# 4_2_-__2024-11-22.net
KiCad netlist of a schematic drawn in Altium Designer
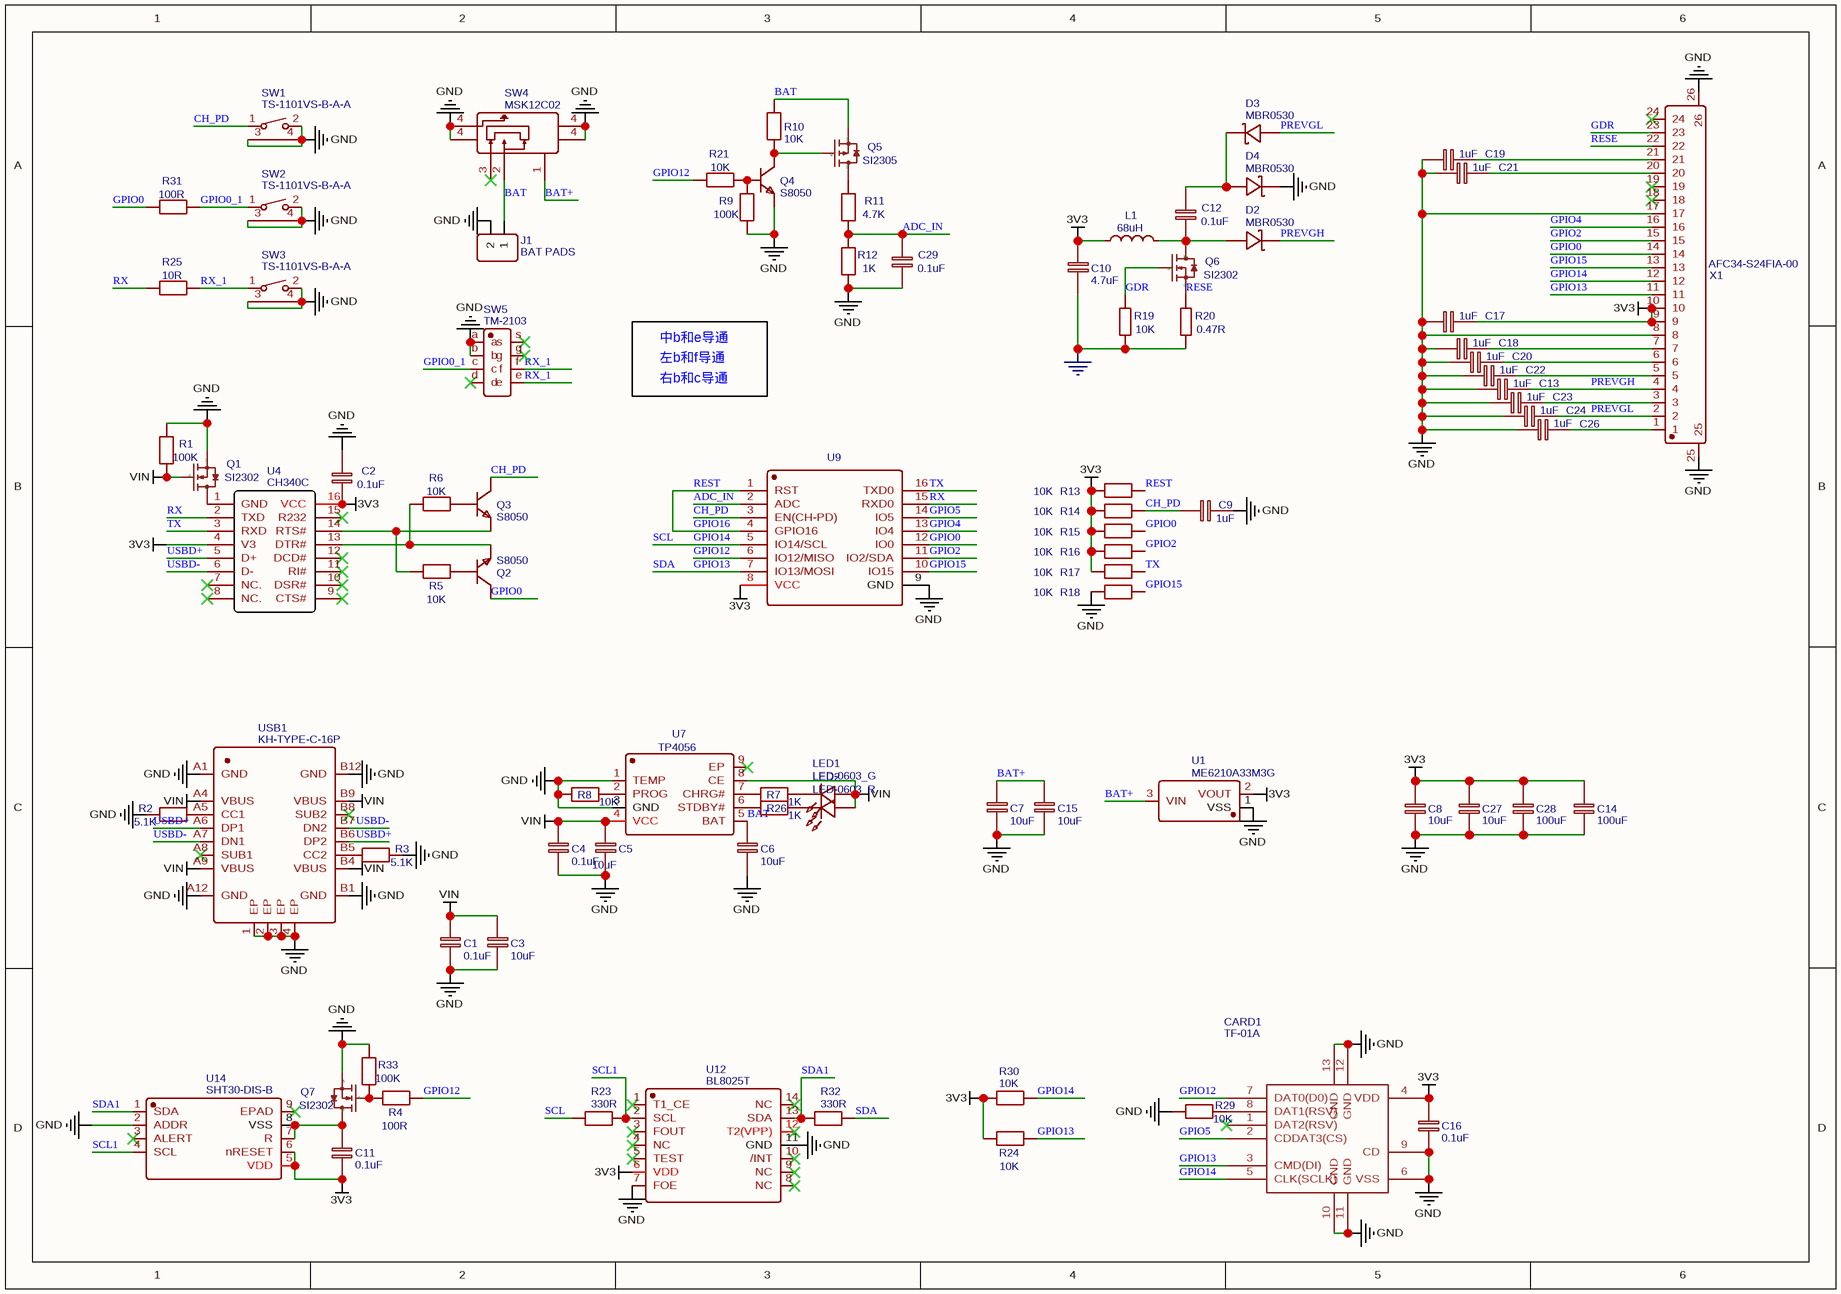
[diagram p0: 4.2寸墨水屏-兼容甘草酸不酸_2024-11-22.schdoc]

(export (version "E")
  (design (tool "Eeschema 10.0.6"))
  (components
    (comp (ref "C1")
      (value "0.1uF")
      (fields (field (name "CONTRIBUTOR") "LCEDA_Lib"))
      (libsource (lib "altium-import") (part "root_3_0.1uF_"))
    )
    (comp (ref "C2")
      (value "0.1uF")
      (fields (field (name "CONTRIBUTOR") "LCEDA_Lib"))
      (libsource (lib "altium-import") (part "root_1_0.1uF_"))
    )
    (comp (ref "C3")
      (value "10uF")
      (fields (field (name "CONTRIBUTOR") "LCEDA_Lib"))
      (libsource (lib "altium-import") (part "root_3_10uF_"))
    )
    (comp (ref "C4")
      (value "0.1uF")
      (fields (field (name "CONTRIBUTOR") "LCEDA_Lib"))
      (libsource (lib "altium-import") (part "root_3_0.1uF_"))
    )
    (comp (ref "C5")
      (value "10uF")
      (fields (field (name "CONTRIBUTOR") "LCEDA_Lib"))
      (libsource (lib "altium-import") (part "root_3_10uF_"))
    )
    (comp (ref "C6")
      (value "10uF")
      (fields (field (name "CONTRIBUTOR") "LCEDA_Lib"))
      (libsource (lib "altium-import") (part "root_3_10uF_"))
    )
    (comp (ref "C7")
      (value "10uF")
      (fields (field (name "CONTRIBUTOR") "LCEDA_Lib"))
      (libsource (lib "altium-import") (part "root_3_10uF_"))
    )
    (comp (ref "C8")
      (value "10uF")
      (fields (field (name "CONTRIBUTOR") "LCEDA_Lib"))
      (libsource (lib "altium-import") (part "root_1_10uF_"))
    )
    (comp (ref "C9")
      (value "1uF")
      (fields (field (name "CONTRIBUTOR") "LCEDA_Lib"))
      (libsource (lib "altium-import") (part "root_0_1uF_"))
    )
    (comp (ref "C10")
      (value "4.7uF")
      (fields
        (field (name "MANUFACTURER PART") "CL10A475MP5LNNC")
        (field (name "MANUFACTURER") "Samsung Electro-Mechanics")
      )
      (libsource (lib "altium-import") (part "root_0_4.7uF_"))
    )
    (comp (ref "C11")
      (value "0.1uF")
      (fields (field (name "CONTRIBUTOR") "LCEDA_Lib"))
      (libsource (lib "altium-import") (part "root_1_0.1uF_"))
    )
    (comp (ref "C12")
      (value "0.1uF")
      (fields (field (name "CONTRIBUTOR") "LCEDA_Lib"))
      (libsource (lib "altium-import") (part "root_1_0.1uF_"))
    )
    (comp (ref "C13")
      (value "1uF")
      (fields (field (name "CONTRIBUTOR") "LCEDA_Lib"))
      (libsource (lib "altium-import") (part "root_0_1uF_"))
    )
    (comp (ref "C14")
      (value "100uF")
      (fields (field (name "CONTRIBUTOR") "LCEDA_Lib"))
      (libsource (lib "altium-import") (part "root_1_100uF_"))
    )
    (comp (ref "C15")
      (value "10uF")
      (fields (field (name "CONTRIBUTOR") "LCEDA_Lib"))
      (libsource (lib "altium-import") (part "root_3_10uF_"))
    )
    (comp (ref "C16")
      (value "0.1uF")
      (fields (field (name "CONTRIBUTOR") "LCEDA_Lib"))
      (libsource (lib "altium-import") (part "root_1_0.1uF_"))
    )
    (comp (ref "C17")
      (value "1uF")
      (fields (field (name "CONTRIBUTOR") "LCEDA_Lib"))
      (libsource (lib "altium-import") (part "root_0_1uF_"))
    )
    (comp (ref "C18")
      (value "1uF")
      (fields (field (name "CONTRIBUTOR") "LCEDA_Lib"))
      (libsource (lib "altium-import") (part "root_0_1uF_"))
    )
    (comp (ref "C19")
      (value "1uF")
      (fields (field (name "CONTRIBUTOR") "LCEDA_Lib"))
      (libsource (lib "altium-import") (part "root_0_1uF_"))
    )
    (comp (ref "C20")
      (value "1uF")
      (fields (field (name "CONTRIBUTOR") "LCEDA_Lib"))
      (libsource (lib "altium-import") (part "root_0_1uF_"))
    )
    (comp (ref "C21")
      (value "1uF")
      (fields (field (name "CONTRIBUTOR") "LCEDA_Lib"))
      (libsource (lib "altium-import") (part "root_0_1uF_"))
    )
    (comp (ref "C22")
      (value "1uF")
      (fields (field (name "CONTRIBUTOR") "LCEDA_Lib"))
      (libsource (lib "altium-import") (part "root_0_1uF_"))
    )
    (comp (ref "C23")
      (value "1uF")
      (fields (field (name "CONTRIBUTOR") "LCEDA_Lib"))
      (libsource (lib "altium-import") (part "root_0_1uF_"))
    )
    (comp (ref "C24")
      (value "1uF")
      (fields (field (name "CONTRIBUTOR") "LCEDA_Lib"))
      (libsource (lib "altium-import") (part "root_0_1uF_"))
    )
    (comp (ref "C26")
      (value "1uF")
      (fields (field (name "CONTRIBUTOR") "LCEDA_Lib"))
      (libsource (lib "altium-import") (part "root_0_1uF_"))
    )
    (comp (ref "C27")
      (value "10uF")
      (fields (field (name "CONTRIBUTOR") "LCEDA_Lib"))
      (libsource (lib "altium-import") (part "root_1_10uF_"))
    )
    (comp (ref "C28")
      (value "100uF")
      (fields (field (name "CONTRIBUTOR") "LCEDA_Lib"))
      (libsource (lib "altium-import") (part "root_1_100uF_"))
    )
    (comp (ref "C29")
      (value "0.1uF")
      (fields (field (name "CONTRIBUTOR") "LCEDA_Lib"))
      (libsource (lib "altium-import") (part "root_1_0.1uF_"))
    )
    (comp (ref "CARD1")
      (value "TF-01A")
      (fields (field (name "MANUFACTURER") "韩国韩荣"))
      (libsource (lib "altium-import") (part "root_0_TF-01A_"))
    )
    (comp (ref "D2") (value "MBR0530") (libsource (lib "altium-import") (part "root_0_MBR0530_")))
    (comp (ref "D3") (value "MBR0530") (libsource (lib "altium-import") (part "root_2_MBR0530_")))
    (comp (ref "D4") (value "MBR0530") (libsource (lib "altium-import") (part "root_0_MBR0530_")))
    (comp (ref "J1")
      (value "BAT PADS")
      (fields (field (name "CONTRIBUTOR") "LCEDA_Lib"))
      (libsource (lib "altium-import") (part "root_3_BAT PADS_"))
    )
    (comp (ref "L1")
      (value "68uH")
      (fields
        (field (name "MANUFACTURER") "DMBJ(振宝佳)")
        (field (name "MANUFACTURER PART") "CD32-680M")
        (field (name "CONTRIBUTOR") "LCSC")
      )
      (libsource (lib "altium-import") (part "root_0_68uH_"))
    )
    (comp (ref "LED1")
      (value "LED-0603_G")
      (fields
        (field (name "MANUFACTURER") "EVERLIGHT(台湾亿光)")
        (field (name "MANUFACTURER PART") "19-217/GHC-YR1S2/3T")
        (field (name "CONTRIBUTOR") "LCEDA_Lib")
      )
      (libsource (lib "altium-import") (part "root_2_LED-0603_G_"))
    )
    (comp (ref "LED2")
      (value "LED-0603_R")
      (fields
        (field (name "MANUFACTURER") "EVERLIGHT(台湾亿光)")
        (field (name "MANUFACTURER PART") "19-217/R6C-AL1M2VY/3T")
        (field (name "CONTRIBUTOR") "LCEDA_01")
      )
      (libsource (lib "altium-import") (part "root_2_LED-0603_R_"))
    )
    (comp (ref "Q1")
      (value "SI2302")
      (fields (field (name "MANUFACTURER") "Hottech") (field (name "CONTRIBUTOR") "LCSC"))
      (libsource (lib "") (part "root_2_SI2302__1"))
    )
    (comp (ref "Q2")
      (value "S8050")
      (fields (field (name "MANUFACTURER") "CJ(江苏长电/长晶)") (field (name "MANUFACTURER PART") "S8050 J3Y"))
      (libsource (lib "") (part "root_0_S8050__1"))
    )
    (comp (ref "Q3")
      (value "S8050")
      (fields (field (name "MANUFACTURER") "CJ(江苏长电/长晶)") (field (name "MANUFACTURER PART") "S8050 J3Y"))
      (libsource (lib "altium-import") (part "root_0_S8050_"))
    )
    (comp (ref "Q4")
      (value "S8050")
      (fields (field (name "MANUFACTURER") "CJ(江苏长电/长晶)") (field (name "MANUFACTURER PART") "S8050 J3Y"))
      (libsource (lib "altium-import") (part "root_0_S8050_"))
    )
    (comp (ref "Q5")
      (value "SI2305")
      (fields (field (name "MANUFACTURER") "Hottech(合科泰)") (field (name "CONTRIBUTOR") "LCSC"))
      (libsource (lib "altium-import") (part "root_0_SI2305_"))
    )
    (comp (ref "Q6")
      (value "SI2302")
      (fields (field (name "MANUFACTURER") "Hottech") (field (name "CONTRIBUTOR") "LCSC"))
      (libsource (lib "altium-import") (part "root_2_SI2302_"))
    )
    (comp (ref "Q7")
      (value "SI2302")
      (fields (field (name "MANUFACTURER") "Hottech") (field (name "CONTRIBUTOR") "LCSC"))
      (libsource (lib "altium-import") (part "root_0_SI2302_"))
    )
    (comp (ref "R1")
      (value "100K")
      (fields (field (name "CONTRIBUTOR") "LCEDA_Lib"))
      (libsource (lib "altium-import") (part "root_1_100K_"))
    )
    (comp (ref "R2")
      (value "5.1K")
      (fields (field (name "CONTRIBUTOR") "LCEDA_Lib"))
      (libsource (lib "altium-import") (part "root_0_5.1K_"))
    )
    (comp (ref "R3")
      (value "5.1K")
      (fields (field (name "CONTRIBUTOR") "LCEDA_Lib"))
      (libsource (lib "altium-import") (part "root_0_5.1K_"))
    )
    (comp (ref "R4")
      (value "100R")
      (fields (field (name "CONTRIBUTOR") "LCEDA_Lib"))
      (libsource (lib "altium-import") (part "root_2_100R_"))
    )
    (comp (ref "R5")
      (value "10K")
      (fields (field (name "CONTRIBUTOR") "LCEDA_Lib"))
      (libsource (lib "altium-import") (part "root_0_10K_"))
    )
    (comp (ref "R6")
      (value "10K")
      (fields (field (name "CONTRIBUTOR") "LCEDA_Lib"))
      (libsource (lib "altium-import") (part "root_0_10K_"))
    )
    (comp (ref "R7")
      (value "1K")
      (fields (field (name "CONTRIBUTOR") "LCEDA_Lib"))
      (libsource (lib "altium-import") (part "root_0_1K_"))
    )
    (comp (ref "R8")
      (value "10K")
      (fields (field (name "CONTRIBUTOR") "LCEDA_Lib"))
      (libsource (lib "altium-import") (part "root_0_10K_"))
    )
    (comp (ref "R9")
      (value "100K")
      (fields (field (name "CONTRIBUTOR") "LCEDA_Lib"))
      (libsource (lib "altium-import") (part "root_1_100K_"))
    )
    (comp (ref "R10")
      (value "10K")
      (fields (field (name "CONTRIBUTOR") "LCEDA_Lib"))
      (libsource (lib "") (part "root_1_10K__1"))
    )
    (comp (ref "R11")
      (value "4.7K")
      (fields (field (name "CONTRIBUTOR") "LCEDA_Lib"))
      (libsource (lib "altium-import") (part "root_1_4.7K_"))
    )
    (comp (ref "R12")
      (value "1K")
      (fields (field (name "CONTRIBUTOR") "LCEDA_Lib"))
      (libsource (lib "altium-import") (part "root_1_1K_"))
    )
    (comp (ref "R13")
      (value "10K")
      (fields (field (name "CONTRIBUTOR") "LCEDA_Lib"))
      (libsource (lib "altium-import") (part "root_0_10K_"))
    )
    (comp (ref "R14")
      (value "10K")
      (fields (field (name "CONTRIBUTOR") "LCEDA_Lib"))
      (libsource (lib "altium-import") (part "root_0_10K_"))
    )
    (comp (ref "R15")
      (value "10K")
      (fields (field (name "CONTRIBUTOR") "LCEDA_Lib"))
      (libsource (lib "altium-import") (part "root_0_10K_"))
    )
    (comp (ref "R16")
      (value "10K")
      (fields (field (name "CONTRIBUTOR") "LCEDA_Lib"))
      (libsource (lib "altium-import") (part "root_0_10K_"))
    )
    (comp (ref "R17")
      (value "10K")
      (fields (field (name "CONTRIBUTOR") "LCEDA_Lib"))
      (libsource (lib "altium-import") (part "root_0_10K_"))
    )
    (comp (ref "R18")
      (value "10K")
      (fields (field (name "CONTRIBUTOR") "LCEDA_Lib"))
      (libsource (lib "altium-import") (part "root_0_10K_"))
    )
    (comp (ref "R19")
      (value "10K")
      (fields
        (field (name "MANUFACTURER PART") "CRCW060310K0JNEA")
        (field (name "MANUFACTURER") "Vishay Intertech")
      )
      (libsource (lib "altium-import") (part "root_1_10K_"))
    )
    (comp (ref "R20")
      (value "0.47R")
      (fields
        (field (name "MANUFACTURER PART") "CR0603F0R47P05")
        (field (name "MANUFACTURER") "Ever Ohms Tech")
      )
      (libsource (lib "altium-import") (part "root_1_0.47R_"))
    )
    (comp (ref "R21")
      (value "10K")
      (fields (field (name "CONTRIBUTOR") "LCEDA_Lib"))
      (libsource (lib "altium-import") (part "root_0_10K_"))
    )
    (comp (ref "R23")
      (value "330R")
      (fields (field (name "CONTRIBUTOR") "LCEDA_Lib"))
      (libsource (lib "altium-import") (part "root_0_330R_"))
    )
    (comp (ref "R24")
      (value "10K")
      (fields (field (name "CONTRIBUTOR") "LCEDA_Lib"))
      (libsource (lib "altium-import") (part "root_2_10K_"))
    )
    (comp (ref "R25")
      (value "10R")
      (fields (field (name "CONTRIBUTOR") "LCEDA_Lib"))
      (libsource (lib "altium-import") (part "root_0_10R_"))
    )
    (comp (ref "R26")
      (value "1K")
      (fields (field (name "CONTRIBUTOR") "LCEDA_Lib"))
      (libsource (lib "altium-import") (part "root_0_1K_"))
    )
    (comp (ref "R29")
      (value "10K")
      (fields (field (name "CONTRIBUTOR") "LCEDA_Lib"))
      (libsource (lib "altium-import") (part "root_0_10K_"))
    )
    (comp (ref "R30")
      (value "10K")
      (fields (field (name "CONTRIBUTOR") "LCEDA_Lib"))
      (libsource (lib "altium-import") (part "root_2_10K_"))
    )
    (comp (ref "R31")
      (value "100R")
      (fields (field (name "CONTRIBUTOR") "LCEDA_Lib"))
      (libsource (lib "altium-import") (part "root_0_100R_"))
    )
    (comp (ref "R32")
      (value "330R")
      (fields (field (name "CONTRIBUTOR") "LCEDA_Lib"))
      (libsource (lib "altium-import") (part "root_0_330R_"))
    )
    (comp (ref "R33")
      (value "100K")
      (fields (field (name "CONTRIBUTOR") "LCEDA_Lib"))
      (libsource (lib "altium-import") (part "root_1_100K_"))
    )
    (comp (ref "SW1")
      (value "TS-1101VS-B-A-A")
      (fields (field (name "MANUFACTURER") "XKB Enterprise") (field (name "CONTRIBUTOR") "LCSC"))
      (libsource (lib "altium-import") (part "root_0_TS-1101VS-B-A-A_"))
    )
    (comp (ref "SW2")
      (value "TS-1101VS-B-A-A")
      (fields (field (name "MANUFACTURER") "XKB Enterprise") (field (name "CONTRIBUTOR") "LCSC"))
      (libsource (lib "altium-import") (part "root_0_TS-1101VS-B-A-A_"))
    )
    (comp (ref "SW3")
      (value "TS-1101VS-B-A-A")
      (fields (field (name "MANUFACTURER") "XKB Enterprise") (field (name "CONTRIBUTOR") "LCSC"))
      (libsource (lib "altium-import") (part "root_0_TS-1101VS-B-A-A_"))
    )
    (comp (ref "SW4")
      (value "MSK12C02")
      (fields (field (name "MANUFACTURER") "SHOU HAN") (field (name "CONTRIBUTOR") "LCSC"))
      (libsource (lib "altium-import") (part "root_2_MSK12C02_"))
    )
    (comp (ref "SW5")
      (value "TM-2103")
      (fields (field (name "MANUFACTURER") "XKB Connectivity(中国星坤)") (field (name "CONTRIBUTOR") "LCSC"))
      (libsource (lib "altium-import") (part "root_0_TM-2103_"))
    )
    (comp (ref "U1")
      (value "ME6210A33M3G")
      (fields (field (name "MANUFACTURER") "MICRONE(南京微盟)") (field (name "CONTRIBUTOR") "LCSC"))
      (libsource (lib "altium-import") (part "root_2_ME6210A33M3G_"))
    )
    (comp (ref "U4")
      (value "CH340C")
      (fields (field (name "MANUFACTURER") "WCH(南京沁恒)"))
      (libsource (lib "altium-import") (part "root_0_CH340C_"))
    )
    (comp (ref "U7")
      (value "TP4056")
      (fields (field (name "MANUFACTURER") "UMW(友台半导体)") (field (name "CONTRIBUTOR") "LCSC"))
      (libsource (lib "altium-import") (part "root_0_TP4056_"))
    )
    (comp (ref "U9")
      (value "ESP8266模组标注版")
      (fields (field (name "CONTRIBUTOR") "SakuraNeko"))
      (libsource (lib "altium-import") (part "root_0_ESP8266模组标注版_"))
    )
    (comp (ref "U12")
      (value "BL8025T")
      (fields (field (name "MANUFACTURER") "BL"))
      (libsource (lib "altium-import") (part "root_0_BL8025T_"))
    )
    (comp (ref "U14")
      (value "SHT30-DIS-B")
      (fields
        (field (name "MANUFACTURER") "Sensirion(瑞士盛思锐)")
        (field (name "MANUFACTURER PART") "SHT30-DIS-B2.5KS")
      )
      (libsource (lib "altium-import") (part "root_0_SHT30-DIS-B_"))
    )
    (comp (ref "USB1")
      (value "KH-TYPE-C-16P")
      (fields (field (name "MANUFACTURER") "kinghelm(金航标)") (field (name "CONTRIBUTOR") "LCSC"))
      (libsource (lib "altium-import") (part "root_0_KH-TYPE-C-16P_"))
    )
    (comp (ref "X1")
      (value "AFC34-S24FIA-00")
      (fields (field (name "MANUFACTURER") "JS(钜硕电子)") (field (name "CONTRIBUTOR") "LCSC"))
      (libsource (lib "altium-import") (part "root_0_AFC34-S24FIA-00_"))
    )
  )
  (nets
    (net (code "1") (name "/ADC_IN") (class "Default")
      (node (ref "C29") (pin "2") (pinfunction "2_2") (pintype "passive"))
      (node (ref "R11") (pin "1") (pinfunction "1_1") (pintype "passive"))
      (node (ref "R12") (pin "2") (pinfunction "2_2") (pintype "passive"))
      (node (ref "U9") (pin "2") (pinfunction "ADC_2") (pintype "passive"))
    )
    (net (code "2") (name "/BAT") (class "Default")
      (node (ref "C6") (pin "1") (pinfunction "1_1") (pintype "passive"))
      (node (ref "J1") (pin "1") (pinfunction "1_1") (pintype "passive"))
      (node (ref "Q5") (pin "2") (pinfunction "S_2") (pintype "passive"))
      (node (ref "R10") (pin "2") (pinfunction "2_2") (pintype "passive"))
      (node (ref "SW4") (pin "2") (pinfunction "2_2") (pintype "passive"))
      (node (ref "U7") (pin "5") (pinfunction "BAT_5") (pintype "passive"))
    )
    (net (code "3") (name "/BAT+") (class "Default")
      (node (ref "C15") (pin "1") (pinfunction "1_1") (pintype "passive"))
      (node (ref "C7") (pin "1") (pinfunction "1_1") (pintype "passive"))
      (node (ref "SW4") (pin "1") (pinfunction "1_1") (pintype "passive"))
      (node (ref "U1") (pin "3") (pinfunction "VIN_3") (pintype "passive"))
    )
    (net (code "4") (name "/CH_PD") (class "Default")
      (node (ref "C9") (pin "1") (pinfunction "1_1") (pintype "passive"))
      (node (ref "Q3") (pin "3") (pinfunction "C_3") (pintype "passive"))
      (node (ref "R14") (pin "2") (pinfunction "2_2") (pintype "passive"))
      (node (ref "SW1") (pin "1") (pinfunction "1_1") (pintype "passive"))
      (node (ref "U9") (pin "3") (pinfunction "EN(CH-PD)_3") (pintype "passive"))
    )
    (net (code "5") (name "/GDR") (class "Default")
      (node (ref "Q6") (pin "1") (pinfunction "G_1") (pintype "passive"))
      (node (ref "R19") (pin "2") (pinfunction "2_2") (pintype "passive"))
      (node (ref "X1") (pin "23") (pinfunction "23_23") (pintype "passive"))
    )
    (net (code "6") (name "/GPIO0") (class "Default")
      (node (ref "Q2") (pin "3") (pinfunction "C_3") (pintype "passive"))
      (node (ref "R15") (pin "2") (pinfunction "2_2") (pintype "passive"))
      (node (ref "R31") (pin "1") (pinfunction "1_1") (pintype "passive"))
      (node (ref "U9") (pin "12") (pinfunction "IO0_12") (pintype "passive"))
      (node (ref "X1") (pin "14") (pinfunction "14_14") (pintype "passive"))
    )
    (net (code "7") (name "/GPIO0_1") (class "Default")
      (node (ref "R31") (pin "2") (pinfunction "2_2") (pintype "passive"))
      (node (ref "SW2") (pin "1") (pinfunction "1_1") (pintype "passive"))
      (node (ref "SW5") (pin "c") (pinfunction "c_c") (pintype "passive"))
    )
    (net (code "8") (name "/GPIO2") (class "Default")
      (node (ref "R16") (pin "2") (pinfunction "2_2") (pintype "passive"))
      (node (ref "U9") (pin "11") (pinfunction "IO2/SDA_11") (pintype "passive"))
      (node (ref "X1") (pin "15") (pinfunction "15_15") (pintype "passive"))
    )
    (net (code "9") (name "/GPIO4") (class "Default")
      (node (ref "U9") (pin "13") (pinfunction "IO4_13") (pintype "passive"))
      (node (ref "X1") (pin "16") (pinfunction "16_16") (pintype "passive"))
    )
    (net (code "10") (name "/GPIO5") (class "Default")
      (node (ref "CARD1") (pin "2") (pinfunction "CDDAT3(CS)_2") (pintype "passive"))
      (node (ref "U9") (pin "14") (pinfunction "IO5_14") (pintype "passive"))
    )
    (net (code "11") (name "/GPIO12") (class "Default")
      (node (ref "CARD1") (pin "7") (pinfunction "DAT0(D0)_7") (pintype "passive"))
      (node (ref "R21") (pin "1") (pinfunction "1_1") (pintype "passive"))
      (node (ref "R4") (pin "1") (pinfunction "1_1") (pintype "passive"))
      (node (ref "U9") (pin "6") (pinfunction "IO12/MISO_6") (pintype "passive"))
    )
    (net (code "12") (name "/GPIO13") (class "Default")
      (node (ref "CARD1") (pin "3") (pinfunction "CMD(DI)_3") (pintype "passive"))
      (node (ref "R24") (pin "1") (pinfunction "1_1") (pintype "passive"))
      (node (ref "R32") (pin "2") (pinfunction "2_2") (pintype "passive"))
      (node (ref "U9") (pin "7") (pinfunction "IO13/MOSI_7") (pintype "passive"))
      (node (ref "X1") (pin "11") (pinfunction "11_11") (pintype "passive"))
    )
    (net (code "13") (name "/GPIO14") (class "Default")
      (node (ref "CARD1") (pin "5") (pinfunction "CLK(SCLK)_5") (pintype "passive"))
      (node (ref "R23") (pin "1") (pinfunction "1_1") (pintype "passive"))
      (node (ref "R30") (pin "1") (pinfunction "1_1") (pintype "passive"))
      (node (ref "U9") (pin "5") (pinfunction "IO14/SCL_5") (pintype "passive"))
      (node (ref "X1") (pin "12") (pinfunction "12_12") (pintype "passive"))
    )
    (net (code "14") (name "/GPIO15") (class "Default")
      (node (ref "R18") (pin "2") (pinfunction "2_2") (pintype "passive"))
      (node (ref "U9") (pin "10") (pinfunction "IO15_10") (pintype "passive"))
      (node (ref "X1") (pin "13") (pinfunction "13_13") (pintype "passive"))
    )
    (net (code "15") (name "/GPIO16") (class "Default")
      (node (ref "R13") (pin "2") (pinfunction "2_2") (pintype "passive"))
      (node (ref "U9") (pin "1") (pinfunction "RST_1") (pintype "passive"))
      (node (ref "U9") (pin "4") (pinfunction "GPIO16_4") (pintype "passive"))
    )
    (net (code "16") (name "/PREVGH") (class "Default")
      (node (ref "C13") (pin "2") (pinfunction "2_2") (pintype "passive"))
      (node (ref "D2") (pin "2") (pinfunction "K_2") (pintype "passive"))
      (node (ref "X1") (pin "4") (pinfunction "4_4") (pintype "passive"))
    )
    (net (code "17") (name "/PREVGL") (class "Default")
      (node (ref "C24") (pin "2") (pinfunction "2_2") (pintype "passive"))
      (node (ref "D3") (pin "1") (pinfunction "A_1") (pintype "passive"))
      (node (ref "X1") (pin "2") (pinfunction "2_2") (pintype "passive"))
    )
    (net (code "18") (name "/RESE") (class "Default")
      (node (ref "Q6") (pin "2") (pinfunction "S_2") (pintype "passive"))
      (node (ref "R20") (pin "2") (pinfunction "2_2") (pintype "passive"))
      (node (ref "X1") (pin "22") (pinfunction "22_22") (pintype "passive"))
    )
    (net (code "19") (name "/RX") (class "Default")
      (node (ref "R25") (pin "1") (pinfunction "1_1") (pintype "passive"))
      (node (ref "U4") (pin "2") (pinfunction "TXD_2") (pintype "passive"))
      (node (ref "U9") (pin "15") (pinfunction "RXD0_15") (pintype "passive"))
    )
    (net (code "20") (name "/RX_1") (class "Default")
      (node (ref "R25") (pin "2") (pinfunction "2_2") (pintype "passive"))
      (node (ref "SW3") (pin "1") (pinfunction "1_1") (pintype "passive"))
      (node (ref "SW5") (pin "e") (pinfunction "e_e") (pintype "passive"))
      (node (ref "SW5") (pin "f") (pinfunction "f_f") (pintype "passive"))
    )
    (net (code "21") (name "/SCL1") (class "Default")
      (node (ref "R23") (pin "2") (pinfunction "2_2") (pintype "passive"))
      (node (ref "U12") (pin "2") (pinfunction "SCL_2") (pintype "passive"))
      (node (ref "U14") (pin "4") (pinfunction "SCL_4") (pintype "passive"))
    )
    (net (code "22") (name "/SDA1") (class "Default")
      (node (ref "R32") (pin "1") (pinfunction "1_1") (pintype "passive"))
      (node (ref "U12") (pin "13") (pinfunction "SDA_13") (pintype "passive"))
      (node (ref "U14") (pin "1") (pinfunction "SDA_1") (pintype "passive"))
    )
    (net (code "23") (name "/TX") (class "Default")
      (node (ref "R17") (pin "2") (pinfunction "2_2") (pintype "passive"))
      (node (ref "U4") (pin "3") (pinfunction "RXD_3") (pintype "passive"))
      (node (ref "U9") (pin "16") (pinfunction "TXD0_16") (pintype "passive"))
    )
    (net (code "24") (name "/USBD+") (class "Default")
      (node (ref "U4") (pin "5") (pinfunction "D+_5") (pintype "passive"))
      (node (ref "USB1") (pin "A6") (pinfunction "DP1_A6") (pintype "passive"))
      (node (ref "USB1") (pin "B6") (pinfunction "DP2_B6") (pintype "passive"))
    )
    (net (code "25") (name "/USBD-") (class "Default")
      (node (ref "U4") (pin "6") (pinfunction "D-_6") (pintype "passive"))
      (node (ref "USB1") (pin "A7") (pinfunction "DN1_A7") (pintype "passive"))
      (node (ref "USB1") (pin "B7") (pinfunction "DN2_B7") (pintype "passive"))
    )
    (net (code "26") (name "3V3") (class "Default")
      (node (ref "C10") (pin "1") (pinfunction "1_1") (pintype "passive"))
      (node (ref "C11") (pin "1") (pinfunction "1_1") (pintype "passive"))
      (node (ref "C14") (pin "2") (pinfunction "2_2") (pintype "passive"))
      (node (ref "C16") (pin "2") (pinfunction "2_2") (pintype "passive"))
      (node (ref "C17") (pin "2") (pinfunction "2_2") (pintype "passive"))
      (node (ref "C2") (pin "1") (pinfunction "1_1") (pintype "passive"))
      (node (ref "C27") (pin "2") (pinfunction "2_2") (pintype "passive"))
      (node (ref "C28") (pin "2") (pinfunction "2_2") (pintype "passive"))
      (node (ref "C8") (pin "2") (pinfunction "2_2") (pintype "passive"))
      (node (ref "CARD1") (pin "4") (pinfunction "VDD_4") (pintype "passive"))
      (node (ref "L1") (pin "1") (pinfunction "1_1") (pintype "passive"))
      (node (ref "R13") (pin "1") (pinfunction "1_1") (pintype "passive"))
      (node (ref "R14") (pin "1") (pinfunction "1_1") (pintype "passive"))
      (node (ref "R15") (pin "1") (pinfunction "1_1") (pintype "passive"))
      (node (ref "R16") (pin "1") (pinfunction "1_1") (pintype "passive"))
      (node (ref "R17") (pin "1") (pinfunction "1_1") (pintype "passive"))
      (node (ref "R24") (pin "2") (pinfunction "2_2") (pintype "passive"))
      (node (ref "R30") (pin "2") (pinfunction "2_2") (pintype "passive"))
      (node (ref "U1") (pin "2") (pinfunction "VOUT_2") (pintype "passive"))
      (node (ref "U12") (pin "6") (pinfunction "VDD_6") (pintype "passive"))
      (node (ref "U14") (pin "5") (pinfunction "VDD_5") (pintype "passive"))
      (node (ref "U14") (pin "6") (pinfunction "nRESET_6") (pintype "passive"))
      (node (ref "U4") (pin "16") (pinfunction "VCC_16") (pintype "passive"))
      (node (ref "U4") (pin "4") (pinfunction "V3_4") (pintype "passive"))
      (node (ref "U9") (pin "8") (pinfunction "VCC_8") (pintype "passive"))
      (node (ref "X1") (pin "10") (pinfunction "10_10") (pintype "passive"))
      (node (ref "X1") (pin "9") (pinfunction "9_9") (pintype "passive"))
    )
    (net (code "27") (name "GND") (class "Default")
      (node (ref "C1") (pin "2") (pinfunction "2_2") (pintype "passive"))
      (node (ref "C10") (pin "2") (pinfunction "2_2") (pintype "passive"))
      (node (ref "C13") (pin "1") (pinfunction "1_1") (pintype "passive"))
      (node (ref "C14") (pin "1") (pinfunction "1_1") (pintype "passive"))
      (node (ref "C15") (pin "2") (pinfunction "2_2") (pintype "passive"))
      (node (ref "C16") (pin "1") (pinfunction "1_1") (pintype "passive"))
      (node (ref "C17") (pin "1") (pinfunction "1_1") (pintype "passive"))
      (node (ref "C18") (pin "1") (pinfunction "1_1") (pintype "passive"))
      (node (ref "C19") (pin "1") (pinfunction "1_1") (pintype "passive"))
      (node (ref "C2") (pin "2") (pinfunction "2_2") (pintype "passive"))
      (node (ref "C20") (pin "1") (pinfunction "1_1") (pintype "passive"))
      (node (ref "C21") (pin "1") (pinfunction "1_1") (pintype "passive"))
      (node (ref "C22") (pin "1") (pinfunction "1_1") (pintype "passive"))
      (node (ref "C23") (pin "1") (pinfunction "1_1") (pintype "passive"))
      (node (ref "C24") (pin "1") (pinfunction "1_1") (pintype "passive"))
      (node (ref "C26") (pin "1") (pinfunction "1_1") (pintype "passive"))
      (node (ref "C27") (pin "1") (pinfunction "1_1") (pintype "passive"))
      (node (ref "C28") (pin "1") (pinfunction "1_1") (pintype "passive"))
      (node (ref "C29") (pin "1") (pinfunction "1_1") (pintype "passive"))
      (node (ref "C3") (pin "2") (pinfunction "2_2") (pintype "passive"))
      (node (ref "C4") (pin "2") (pinfunction "2_2") (pintype "passive"))
      (node (ref "C5") (pin "2") (pinfunction "2_2") (pintype "passive"))
      (node (ref "C6") (pin "2") (pinfunction "2_2") (pintype "passive"))
      (node (ref "C7") (pin "2") (pinfunction "2_2") (pintype "passive"))
      (node (ref "C8") (pin "1") (pinfunction "1_1") (pintype "passive"))
      (node (ref "C9") (pin "2") (pinfunction "2_2") (pintype "passive"))
      (node (ref "CARD1") (pin "10") (pinfunction "GND_10") (pintype "passive"))
      (node (ref "CARD1") (pin "11") (pinfunction "GND_11") (pintype "passive"))
      (node (ref "CARD1") (pin "12") (pinfunction "GND_12") (pintype "passive"))
      (node (ref "CARD1") (pin "13") (pinfunction "GND_13") (pintype "passive"))
      (node (ref "CARD1") (pin "6") (pinfunction "VSS_6") (pintype "passive"))
      (node (ref "CARD1") (pin "9") (pinfunction "CD_9") (pintype "passive"))
      (node (ref "D4") (pin "2") (pinfunction "K_2") (pintype "passive"))
      (node (ref "J1") (pin "2") (pinfunction "2_2") (pintype "passive"))
      (node (ref "Q1") (pin "2") (pinfunction "S_2") (pintype "passive"))
      (node (ref "Q4") (pin "2") (pinfunction "E_2") (pintype "passive"))
      (node (ref "Q7") (pin "2") (pinfunction "S_2") (pintype "passive"))
      (node (ref "R1") (pin "2") (pinfunction "2_2") (pintype "passive"))
      (node (ref "R12") (pin "1") (pinfunction "1_1") (pintype "passive"))
      (node (ref "R18") (pin "1") (pinfunction "1_1") (pintype "passive"))
      (node (ref "R19") (pin "1") (pinfunction "1_1") (pintype "passive"))
      (node (ref "R2") (pin "1") (pinfunction "1_1") (pintype "passive"))
      (node (ref "R20") (pin "1") (pinfunction "1_1") (pintype "passive"))
      (node (ref "R29") (pin "1") (pinfunction "1_1") (pintype "passive"))
      (node (ref "R3") (pin "2") (pinfunction "2_2") (pintype "passive"))
      (node (ref "R33") (pin "2") (pinfunction "2_2") (pintype "passive"))
      (node (ref "R8") (pin "1") (pinfunction "1_1") (pintype "passive"))
      (node (ref "R9") (pin "1") (pinfunction "1_1") (pintype "passive"))
      (node (ref "SW1") (pin "2") (pinfunction "2_2") (pintype "passive"))
      (node (ref "SW1") (pin "3") (pinfunction "3_3") (pintype "passive"))
      (node (ref "SW1") (pin "4") (pinfunction "4_4") (pintype "passive"))
      (node (ref "SW2") (pin "2") (pinfunction "2_2") (pintype "passive"))
      (node (ref "SW2") (pin "3") (pinfunction "3_3") (pintype "passive"))
      (node (ref "SW2") (pin "4") (pinfunction "4_4") (pintype "passive"))
      (node (ref "SW3") (pin "2") (pinfunction "2_2") (pintype "passive"))
      (node (ref "SW3") (pin "3") (pinfunction "3_3") (pintype "passive"))
      (node (ref "SW3") (pin "4") (pinfunction "4_4") (pintype "passive"))
      (node (ref "SW4") (pin "4") (pinfunction "4_4") (pintype "passive"))
      (node (ref "SW5") (pin "a") (pinfunction "a_a") (pintype "passive"))
      (node (ref "SW5") (pin "b") (pinfunction "b_b") (pintype "passive"))
      (node (ref "U1") (pin "1") (pinfunction "VSS_1") (pintype "passive"))
      (node (ref "U12") (pin "11") (pinfunction "GND_11") (pintype "passive"))
      (node (ref "U12") (pin "7") (pinfunction "FOE_7") (pintype "passive"))
      (node (ref "U14") (pin "2") (pinfunction "ADDR_2") (pintype "passive"))
      (node (ref "U7") (pin "1") (pinfunction "TEMP_1") (pintype "passive"))
      (node (ref "U7") (pin "3") (pinfunction "GND_3") (pintype "passive"))
      (node (ref "U9") (pin "9") (pinfunction "GND_9") (pintype "passive"))
      (node (ref "USB1") (pin "1") (pinfunction "EP_1") (pintype "passive"))
      (node (ref "USB1") (pin "2") (pinfunction "EP_2") (pintype "passive"))
      (node (ref "USB1") (pin "3") (pinfunction "EP_3") (pintype "passive"))
      (node (ref "USB1") (pin "4") (pinfunction "EP_4") (pintype "passive"))
      (node (ref "USB1") (pin "A1") (pinfunction "GND_A1") (pintype "passive"))
      (node (ref "USB1") (pin "A12") (pinfunction "GND_A12") (pintype "passive"))
      (node (ref "USB1") (pin "B1") (pinfunction "GND_B1") (pintype "passive"))
      (node (ref "USB1") (pin "B12") (pinfunction "GND_B12") (pintype "passive"))
      (node (ref "X1") (pin "17") (pinfunction "17_17") (pintype "passive"))
      (node (ref "X1") (pin "25") (pinfunction "25_25") (pintype "passive"))
      (node (ref "X1") (pin "26") (pinfunction "26_26") (pintype "passive"))
      (node (ref "X1") (pin "8") (pinfunction "8_8") (pintype "passive"))
    )
    (net (code "28") (name "Net-(C18-Pad2)") (class "Default")
      (node (ref "C18") (pin "2") (pinfunction "2_2") (pintype "passive"))
      (node (ref "X1") (pin "7") (pinfunction "7_7") (pintype "passive"))
    )
    (net (code "29") (name "Net-(C19-Pad2)") (class "Default")
      (node (ref "C19") (pin "2") (pinfunction "2_2") (pintype "passive"))
      (node (ref "X1") (pin "21") (pinfunction "21_21") (pintype "passive"))
    )
    (net (code "30") (name "Net-(C20-Pad2)") (class "Default")
      (node (ref "C20") (pin "2") (pinfunction "2_2") (pintype "passive"))
      (node (ref "X1") (pin "6") (pinfunction "6_6") (pintype "passive"))
    )
    (net (code "31") (name "Net-(C21-Pad2)") (class "Default")
      (node (ref "C21") (pin "2") (pinfunction "2_2") (pintype "passive"))
      (node (ref "X1") (pin "20") (pinfunction "20_20") (pintype "passive"))
    )
    (net (code "32") (name "Net-(C22-Pad2)") (class "Default")
      (node (ref "C22") (pin "2") (pinfunction "2_2") (pintype "passive"))
      (node (ref "X1") (pin "5") (pinfunction "5_5") (pintype "passive"))
    )
    (net (code "33") (name "Net-(C23-Pad2)") (class "Default")
      (node (ref "C23") (pin "2") (pinfunction "2_2") (pintype "passive"))
      (node (ref "X1") (pin "3") (pinfunction "3_3") (pintype "passive"))
    )
    (net (code "34") (name "Net-(C26-Pad2)") (class "Default")
      (node (ref "C26") (pin "2") (pinfunction "2_2") (pintype "passive"))
      (node (ref "X1") (pin "1") (pinfunction "1_1") (pintype "passive"))
    )
    (net (code "35") (name "Net-(CARD1-DAT1(RSV))") (class "Default")
      (node (ref "CARD1") (pin "8") (pinfunction "DAT1(RSV)_8") (pintype "passive"))
      (node (ref "R29") (pin "2") (pinfunction "2_2") (pintype "passive"))
    )
    (net (code "36") (name "Net-(D2-A)") (class "Default")
      (node (ref "C12") (pin "1") (pinfunction "1_1") (pintype "passive"))
      (node (ref "D2") (pin "1") (pinfunction "A_1") (pintype "passive"))
      (node (ref "L1") (pin "2") (pinfunction "2_2") (pintype "passive"))
      (node (ref "Q6") (pin "3") (pinfunction "D_3") (pintype "passive"))
    )
    (net (code "37") (name "Net-(D3-K)") (class "Default")
      (node (ref "C12") (pin "2") (pinfunction "2_2") (pintype "passive"))
      (node (ref "D3") (pin "2") (pinfunction "K_2") (pintype "passive"))
      (node (ref "D4") (pin "1") (pinfunction "A_1") (pintype "passive"))
    )
    (net (code "38") (name "Net-(LED1-Pad2)") (class "Default")
      (node (ref "LED1") (pin "2") (pinfunction "2_2") (pintype "passive"))
      (node (ref "R7") (pin "2") (pinfunction "2_2") (pintype "passive"))
    )
    (net (code "39") (name "Net-(LED2-Pad2)") (class "Default")
      (node (ref "LED2") (pin "2") (pinfunction "2_2") (pintype "passive"))
      (node (ref "R26") (pin "2") (pinfunction "2_2") (pintype "passive"))
    )
    (net (code "40") (name "Net-(Q1-D)") (class "Default")
      (node (ref "Q1") (pin "3") (pinfunction "D_3") (pintype "passive"))
      (node (ref "U4") (pin "1") (pinfunction "GND_1") (pintype "passive"))
    )
    (net (code "41") (name "Net-(Q2-B)") (class "Default")
      (node (ref "Q2") (pin "1") (pinfunction "B_1") (pintype "passive"))
      (node (ref "R5") (pin "2") (pinfunction "2_2") (pintype "passive"))
    )
    (net (code "42") (name "Net-(Q2-E)") (class "Default")
      (node (ref "Q2") (pin "2") (pinfunction "E_2") (pintype "passive"))
      (node (ref "R6") (pin "1") (pinfunction "1_1") (pintype "passive"))
      (node (ref "U4") (pin "13") (pinfunction "DTR#_13") (pintype "passive"))
    )
    (net (code "43") (name "Net-(Q3-B)") (class "Default")
      (node (ref "Q3") (pin "1") (pinfunction "B_1") (pintype "passive"))
      (node (ref "R6") (pin "2") (pinfunction "2_2") (pintype "passive"))
    )
    (net (code "44") (name "Net-(Q3-E)") (class "Default")
      (node (ref "Q3") (pin "2") (pinfunction "E_2") (pintype "passive"))
      (node (ref "R5") (pin "1") (pinfunction "1_1") (pintype "passive"))
      (node (ref "U4") (pin "14") (pinfunction "RTS#_14") (pintype "passive"))
    )
    (net (code "45") (name "Net-(Q4-B)") (class "Default")
      (node (ref "Q4") (pin "1") (pinfunction "B_1") (pintype "passive"))
      (node (ref "R21") (pin "2") (pinfunction "2_2") (pintype "passive"))
      (node (ref "R9") (pin "2") (pinfunction "2_2") (pintype "passive"))
    )
    (net (code "46") (name "Net-(Q4-C)") (class "Default")
      (node (ref "Q4") (pin "3") (pinfunction "C_3") (pintype "passive"))
      (node (ref "Q5") (pin "1") (pinfunction "G_1") (pintype "passive"))
      (node (ref "R10") (pin "1") (pinfunction "1_1") (pintype "passive"))
    )
    (net (code "47") (name "Net-(Q5-D)") (class "Default")
      (node (ref "Q5") (pin "3") (pinfunction "D_3") (pintype "passive"))
      (node (ref "R11") (pin "2") (pinfunction "2_2") (pintype "passive"))
    )
    (net (code "48") (name "Net-(Q7-D)") (class "Default")
      (node (ref "C11") (pin "2") (pinfunction "2_2") (pintype "passive"))
      (node (ref "Q7") (pin "3") (pinfunction "D_3") (pintype "passive"))
      (node (ref "U14") (pin "7") (pinfunction "R_7") (pintype "passive"))
      (node (ref "U14") (pin "8") (pinfunction "VSS_8") (pintype "passive"))
    )
    (net (code "49") (name "Net-(Q7-G)") (class "Default")
      (node (ref "Q7") (pin "1") (pinfunction "G_1") (pintype "passive"))
      (node (ref "R33") (pin "1") (pinfunction "1_1") (pintype "passive"))
      (node (ref "R4") (pin "2") (pinfunction "2_2") (pintype "passive"))
    )
    (net (code "50") (name "Net-(U7-CHRG#)") (class "Default")
      (node (ref "R7") (pin "1") (pinfunction "1_1") (pintype "passive"))
      (node (ref "U7") (pin "7") (pinfunction "CHRG#_7") (pintype "passive"))
    )
    (net (code "51") (name "Net-(U7-PROG)") (class "Default")
      (node (ref "R8") (pin "2") (pinfunction "2_2") (pintype "passive"))
      (node (ref "U7") (pin "2") (pinfunction "PROG_2") (pintype "passive"))
    )
    (net (code "52") (name "Net-(U7-STDBY#)") (class "Default")
      (node (ref "R26") (pin "1") (pinfunction "1_1") (pintype "passive"))
      (node (ref "U7") (pin "6") (pinfunction "STDBY#_6") (pintype "passive"))
    )
    (net (code "53") (name "Net-(USB1-CC1)") (class "Default")
      (node (ref "R2") (pin "2") (pinfunction "2_2") (pintype "passive"))
      (node (ref "USB1") (pin "A5") (pinfunction "CC1_A5") (pintype "passive"))
    )
    (net (code "54") (name "Net-(USB1-CC2)") (class "Default")
      (node (ref "R3") (pin "1") (pinfunction "1_1") (pintype "passive"))
      (node (ref "USB1") (pin "B5") (pinfunction "CC2_B5") (pintype "passive"))
    )
    (net (code "55") (name "VIN") (class "Default")
      (node (ref "C1") (pin "1") (pinfunction "1_1") (pintype "passive"))
      (node (ref "C3") (pin "1") (pinfunction "1_1") (pintype "passive"))
      (node (ref "C4") (pin "1") (pinfunction "1_1") (pintype "passive"))
      (node (ref "C5") (pin "1") (pinfunction "1_1") (pintype "passive"))
      (node (ref "LED1") (pin "1") (pinfunction "1_1") (pintype "passive"))
      (node (ref "LED2") (pin "1") (pinfunction "1_1") (pintype "passive"))
      (node (ref "Q1") (pin "1") (pinfunction "G_1") (pintype "passive"))
      (node (ref "R1") (pin "1") (pinfunction "1_1") (pintype "passive"))
      (node (ref "U7") (pin "4") (pinfunction "VCC_4") (pintype "passive"))
      (node (ref "U7") (pin "8") (pinfunction "CE_8") (pintype "passive"))
      (node (ref "USB1") (pin "A4") (pinfunction "VBUS_A4") (pintype "passive"))
      (node (ref "USB1") (pin "A9") (pinfunction "VBUS_A9") (pintype "passive"))
      (node (ref "USB1") (pin "B4") (pinfunction "VBUS_B4") (pintype "passive"))
      (node (ref "USB1") (pin "B9") (pinfunction "VBUS_B9") (pintype "passive"))
    )
    (net (code "56") (name "unconnected-(CARD1-DAT2(RSV)-Pad1)") (class "Default")
      (node (ref "CARD1") (pin "1") (pinfunction "DAT2(RSV)_1") (pintype "passive+no_connect"))
    )
    (net (code "57") (name "unconnected-(SW4-Pad3)") (class "Default")
      (node (ref "SW4") (pin "3") (pinfunction "3_3") (pintype "passive+no_connect"))
    )
    (net (code "58") (name "unconnected-(SW5-Padd)") (class "Default")
      (node (ref "SW5") (pin "d") (pinfunction "d_d") (pintype "passive+no_connect"))
    )
    (net (code "59") (name "unconnected-(SW5-Padg)") (class "Default")
      (node (ref "SW5") (pin "g") (pinfunction "g_g") (pintype "passive+no_connect"))
    )
    (net (code "60") (name "unconnected-(SW5-Pads)") (class "Default")
      (node (ref "SW5") (pin "s") (pinfunction "s_s") (pintype "passive+no_connect"))
    )
    (net (code "61") (name "unconnected-(U4-CTS#-Pad9)") (class "Default")
      (node (ref "U4") (pin "9") (pinfunction "CTS#_9") (pintype "passive+no_connect"))
    )
    (net (code "62") (name "unconnected-(U4-DCD#-Pad12)") (class "Default")
      (node (ref "U4") (pin "12") (pinfunction "DCD#_12") (pintype "passive+no_connect"))
    )
    (net (code "63") (name "unconnected-(U4-DSR#-Pad10)") (class "Default")
      (node (ref "U4") (pin "10") (pinfunction "DSR#_10") (pintype "passive+no_connect"))
    )
    (net (code "64") (name "unconnected-(U4-NC.-Pad7)") (class "Default")
      (node (ref "U4") (pin "7") (pinfunction "NC._7") (pintype "passive+no_connect"))
    )
    (net (code "65") (name "unconnected-(U4-NC.-Pad8)") (class "Default")
      (node (ref "U4") (pin "8") (pinfunction "NC._8") (pintype "passive+no_connect"))
    )
    (net (code "66") (name "unconnected-(U4-R232-Pad15)") (class "Default")
      (node (ref "U4") (pin "15") (pinfunction "R232_15") (pintype "passive+no_connect"))
    )
    (net (code "67") (name "unconnected-(U4-RI#-Pad11)") (class "Default")
      (node (ref "U4") (pin "11") (pinfunction "RI#_11") (pintype "passive+no_connect"))
    )
    (net (code "68") (name "unconnected-(U7-EP-Pad9)") (class "Default")
      (node (ref "U7") (pin "9") (pinfunction "EP_9") (pintype "passive+no_connect"))
    )
    (net (code "69") (name "unconnected-(U12-FOUT-Pad3)") (class "Default")
      (node (ref "U12") (pin "3") (pinfunction "FOUT_3") (pintype "passive+no_connect"))
    )
    (net (code "70") (name "unconnected-(U12-NC-Pad4)") (class "Default")
      (node (ref "U12") (pin "4") (pinfunction "NC_4") (pintype "passive+no_connect"))
    )
    (net (code "71") (name "unconnected-(U12-NC-Pad8)") (class "Default")
      (node (ref "U12") (pin "8") (pinfunction "NC_8") (pintype "passive+no_connect"))
    )
    (net (code "72") (name "unconnected-(U12-NC-Pad9)") (class "Default")
      (node (ref "U12") (pin "9") (pinfunction "NC_9") (pintype "passive+no_connect"))
    )
    (net (code "73") (name "unconnected-(U12-NC-Pad14)") (class "Default")
      (node (ref "U12") (pin "14") (pinfunction "NC_14") (pintype "passive+no_connect"))
    )
    (net (code "74") (name "unconnected-(U12-T1_CE-Pad1)") (class "Default")
      (node (ref "U12") (pin "1") (pinfunction "T1_CE_1") (pintype "passive+no_connect"))
    )
    (net (code "75") (name "unconnected-(U12-T2(VPP)-Pad12)") (class "Default")
      (node (ref "U12") (pin "12") (pinfunction "T2(VPP)_12") (pintype "passive+no_connect"))
    )
    (net (code "76") (name "unconnected-(U12-TEST-Pad5)") (class "Default")
      (node (ref "U12") (pin "5") (pinfunction "TEST_5") (pintype "passive+no_connect"))
    )
    (net (code "77") (name "unconnected-(U12-{slash}INT-Pad10)") (class "Default")
      (node (ref "U12") (pin "10") (pinfunction "/INT_10") (pintype "passive+no_connect"))
    )
    (net (code "78") (name "unconnected-(U14-ALERT-Pad3)") (class "Default")
      (node (ref "U14") (pin "3") (pinfunction "ALERT_3") (pintype "passive+no_connect"))
    )
    (net (code "79") (name "unconnected-(U14-EPAD-Pad9)") (class "Default")
      (node (ref "U14") (pin "9") (pinfunction "EPAD_9") (pintype "passive+no_connect"))
    )
    (net (code "80") (name "unconnected-(USB1-SUB1-PadA8)") (class "Default")
      (node (ref "USB1") (pin "A8") (pinfunction "SUB1_A8") (pintype "passive+no_connect"))
    )
    (net (code "81") (name "unconnected-(USB1-SUB2-PadB8)") (class "Default")
      (node (ref "USB1") (pin "B8") (pinfunction "SUB2_B8") (pintype "passive+no_connect"))
    )
    (net (code "82") (name "unconnected-(X1-Pad18)") (class "Default")
      (node (ref "X1") (pin "18") (pinfunction "18_18") (pintype "passive+no_connect"))
    )
    (net (code "83") (name "unconnected-(X1-Pad19)") (class "Default")
      (node (ref "X1") (pin "19") (pinfunction "19_19") (pintype "passive+no_connect"))
    )
    (net (code "84") (name "unconnected-(X1-Pad24)") (class "Default")
      (node (ref "X1") (pin "24") (pinfunction "24_24") (pintype "passive+no_connect"))
    )
  )
)
